# BG1094_MIPI_CAM.net
KiCad netlist of a schematic drawn in Altium Designer
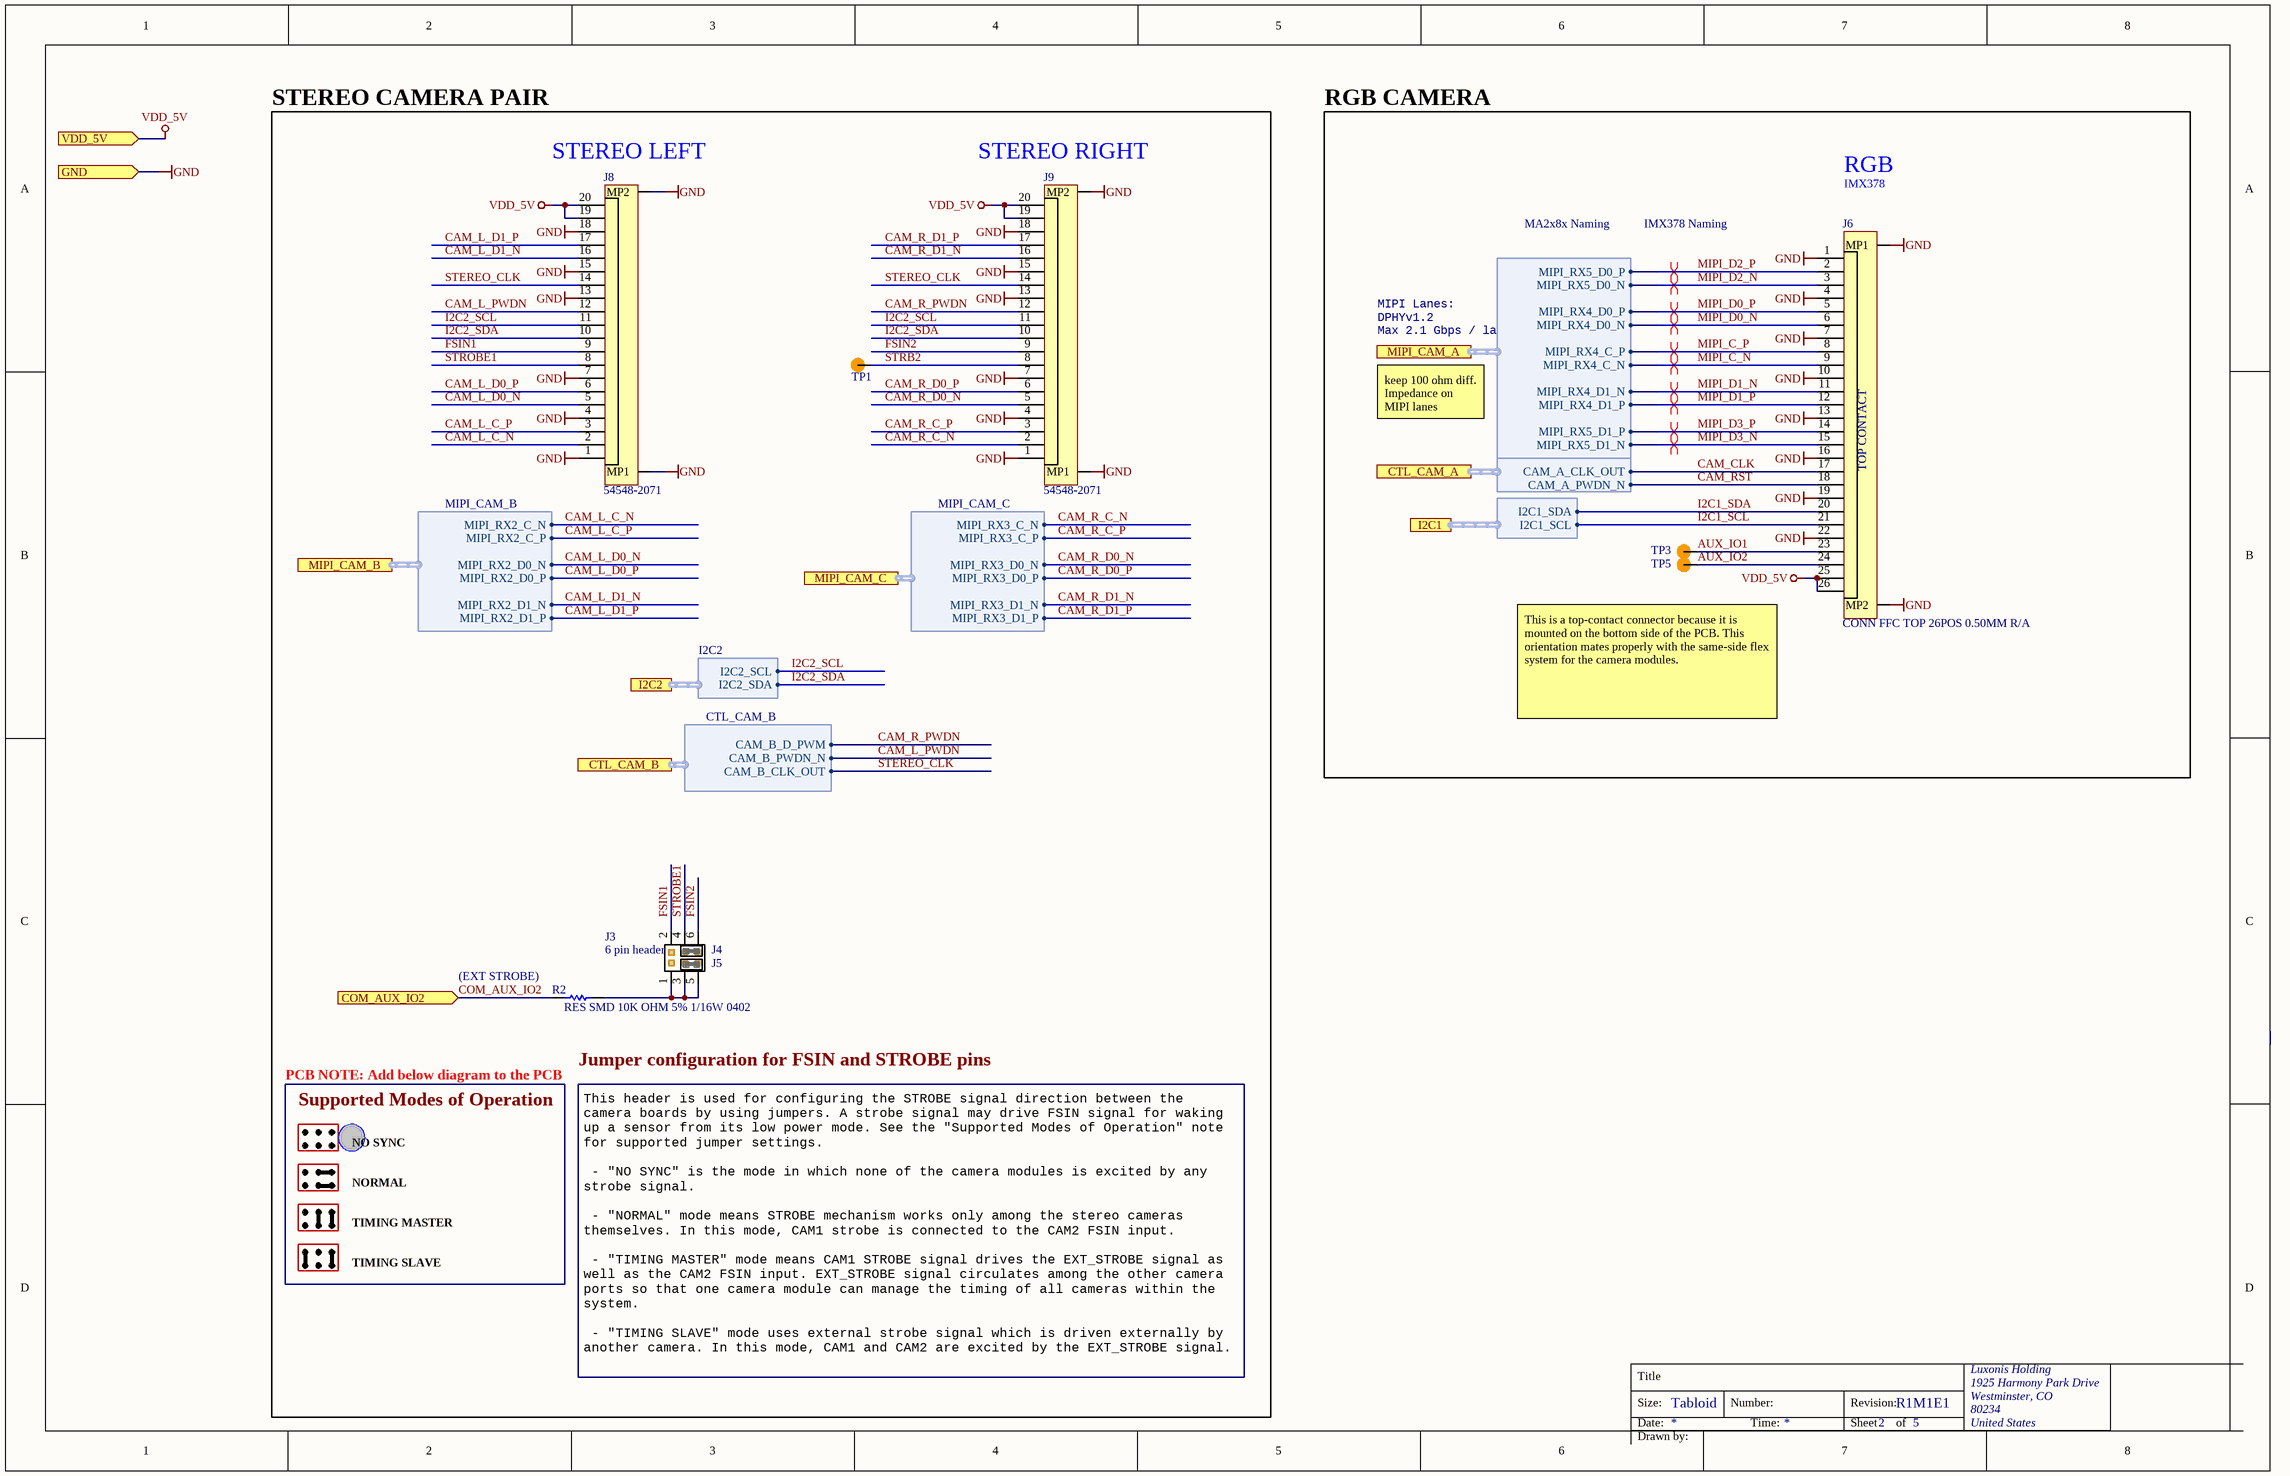
[diagram p0: BG1094_MIPI_CAM.SchDoc]

(export (version "E")
  (design (tool "Eeschema 10.0.6"))
  (components
    (comp (ref "J3")
      (value "6 pin header")
      (footprint "Luxonis:con-20021121-00006C4LF")
      (libsource (lib "Luxonis") (part "HDR_2x3_1.27mm"))
    )
    (comp (ref "J4")
      (value "1.27mm hdr shunt")
      (footprint "Luxonis:HDR_SHUNT_1.27MM")
      (description "CONN SHUNT 1.27MM BLACK (M50-1900005)")
      (libsource (lib "Luxonis") (part "HDR_Shunt_1.27mm"))
    )
    (comp (ref "J5")
      (value "1.27mm hdr shunt")
      (footprint "Luxonis:HDR_SHUNT_1.27MM")
      (description "CONN SHUNT 1.27MM BLACK (M50-1900005)")
      (libsource (lib "Luxonis") (part "HDR_Shunt_1.27mm"))
    )
    (comp (ref "J6")
      (value "CONN FFC TOP 26POS 0.50MM R/A")
      (footprint "BG1094:54550-2671")
      (libsource (lib "BG1094") (part "54550-2671"))
    )
    (comp (ref "J8")
      (value "54548-2071")
      (footprint "Luxonis:545482071")
      (description "FFC & FPC Connectors 0.5 FPC ZIF Hsg Assy ssy 20Ckt EmbsTp Pkg")
      (fields
        (field (name "MANUFACTURER_PART_NUMBER") "54548-2271")
        (field (name "MOUSER PART NUMBER") "538-54548-2271")
      )
      (libsource (lib "Luxonis") (part "54548-2071"))
    )
    (comp (ref "J9")
      (value "54548-2071")
      (footprint "Luxonis:545482071")
      (description "FFC & FPC Connectors 0.5 FPC ZIF Hsg Assy ssy 20Ckt EmbsTp Pkg")
      (fields
        (field (name "MANUFACTURER_PART_NUMBER") "54548-2271")
        (field (name "MOUSER PART NUMBER") "538-54548-2271")
      )
      (libsource (lib "Luxonis") (part "54548-2071"))
    )
    (comp (ref "R2")
      (value "RES SMD 10K OHM 5% 1/16W 0402")
      (footprint "RESC0402(1005)_N")
      (libsource (lib "Luxonis") (part "!RES"))
    )
    (comp (ref "TP1")
      (value "TP_SMD")
      (footprint "TP_0.75MM_SMD_NO-SILK")
      (description "circular pad test point, SMD")
      (libsource (lib "Luxonis") (part "TP_SMD"))
    )
    (comp (ref "TP3")
      (value "TP100_200_NS")
      (footprint "LuxonisMaster:TP100_200_NS")
      (libsource (lib "LuxonisMaster") (part "TEST_POINT"))
    )
    (comp (ref "TP5")
      (value "TP100_200_NS")
      (footprint "LuxonisMaster:TP100_200_NS")
      (libsource (lib "LuxonisMaster") (part "TEST_POINT"))
    )
  )
  (nets
    (net (code "8") (name "/AUX_IO1") (class "Default")
      (node (ref "J6") (pin "23") (pinfunction "23_23") (pintype "passive"))
      (node (ref "TP3") (pin "1") (pintype "passive"))
    )
    (net (code "9") (name "/AUX_IO2") (class "Default")
      (node (ref "J6") (pin "24") (pinfunction "24_24") (pintype "passive"))
      (node (ref "TP5") (pin "1") (pintype "passive"))
    )
    (net (code "10") (name "/CAM_CLK") (class "Default")
      (node (ref "J6") (pin "17") (pinfunction "17_17") (pintype "passive"))
    )
    (net (code "11") (name "/CAM_L_C_N") (class "Default")
      (node (ref "J8") (pin "2") (pinfunction "2_2") (pintype "passive"))
    )
    (net (code "12") (name "/CAM_L_C_P") (class "Default")
      (node (ref "J8") (pin "3") (pinfunction "3_3") (pintype "passive"))
    )
    (net (code "13") (name "/CAM_L_D0_N") (class "Default")
      (node (ref "J8") (pin "5") (pinfunction "5_5") (pintype "passive"))
    )
    (net (code "14") (name "/CAM_L_D0_P") (class "Default")
      (node (ref "J8") (pin "6") (pinfunction "6_6") (pintype "passive"))
    )
    (net (code "15") (name "/CAM_L_D1_N") (class "Default")
      (node (ref "J8") (pin "16") (pinfunction "16_16") (pintype "passive"))
    )
    (net (code "16") (name "/CAM_L_D1_P") (class "Default")
      (node (ref "J8") (pin "17") (pinfunction "17_17") (pintype "passive"))
    )
    (net (code "17") (name "/CAM_L_PWDN") (class "Default")
      (node (ref "J8") (pin "12") (pinfunction "12_12") (pintype "passive"))
    )
    (net (code "18") (name "/CAM_RST") (class "Default")
      (node (ref "J6") (pin "18") (pinfunction "18_18") (pintype "passive"))
    )
    (net (code "19") (name "/CAM_R_C_N") (class "Default")
      (node (ref "J9") (pin "2") (pinfunction "2_2") (pintype "passive"))
    )
    (net (code "20") (name "/CAM_R_C_P") (class "Default")
      (node (ref "J9") (pin "3") (pinfunction "3_3") (pintype "passive"))
    )
    (net (code "21") (name "/CAM_R_D0_N") (class "Default")
      (node (ref "J9") (pin "5") (pinfunction "5_5") (pintype "passive"))
    )
    (net (code "22") (name "/CAM_R_D0_P") (class "Default")
      (node (ref "J9") (pin "6") (pinfunction "6_6") (pintype "passive"))
    )
    (net (code "23") (name "/CAM_R_D1_N") (class "Default")
      (node (ref "J9") (pin "16") (pinfunction "16_16") (pintype "passive"))
    )
    (net (code "24") (name "/CAM_R_D1_P") (class "Default")
      (node (ref "J9") (pin "17") (pinfunction "17_17") (pintype "passive"))
    )
    (net (code "25") (name "/CAM_R_PWDN") (class "Default")
      (node (ref "J9") (pin "12") (pinfunction "12_12") (pintype "passive"))
    )
    (net (code "26") (name "/COM_AUX_IO2") (class "Default")
      (node (ref "R2") (pin "1") (pinfunction "1_1") (pintype "passive"))
    )
    (net (code "27") (name "/FSIN1") (class "Default")
      (node (ref "J3") (pin "2") (pinfunction "2_2") (pintype "passive"))
      (node (ref "J8") (pin "9") (pinfunction "9_9") (pintype "passive"))
    )
    (net (code "28") (name "/FSIN2") (class "Default")
      (node (ref "J3") (pin "6") (pinfunction "6_6") (pintype "passive"))
      (node (ref "J9") (pin "9") (pinfunction "9_9") (pintype "passive"))
    )
    (net (code "29") (name "/I2C1_SCL") (class "Default")
      (node (ref "J6") (pin "21") (pinfunction "21_21") (pintype "passive"))
    )
    (net (code "30") (name "/I2C1_SDA") (class "Default")
      (node (ref "J6") (pin "20") (pinfunction "20_20") (pintype "passive"))
    )
    (net (code "31") (name "/I2C2_SCL") (class "Default")
      (node (ref "J8") (pin "11") (pinfunction "11_11") (pintype "passive"))
      (node (ref "J9") (pin "11") (pinfunction "11_11") (pintype "passive"))
    )
    (net (code "32") (name "/I2C2_SDA") (class "Default")
      (node (ref "J8") (pin "10") (pinfunction "10_10") (pintype "passive"))
      (node (ref "J9") (pin "10") (pinfunction "10_10") (pintype "passive"))
    )
    (net (code "33") (name "/MIPI_C_N") (class "Default")
      (node (ref "J6") (pin "9") (pinfunction "9_9") (pintype "passive"))
    )
    (net (code "34") (name "/MIPI_C_P") (class "Default")
      (node (ref "J6") (pin "8") (pinfunction "8_8") (pintype "passive"))
    )
    (net (code "35") (name "/MIPI_D0_N") (class "Default")
      (node (ref "J6") (pin "6") (pinfunction "6_6") (pintype "passive"))
    )
    (net (code "36") (name "/MIPI_D0_P") (class "Default")
      (node (ref "J6") (pin "5") (pinfunction "5_5") (pintype "passive"))
    )
    (net (code "37") (name "/MIPI_D1_N") (class "Default")
      (node (ref "J6") (pin "11") (pinfunction "11_11") (pintype "passive"))
    )
    (net (code "38") (name "/MIPI_D1_P") (class "Default")
      (node (ref "J6") (pin "12") (pinfunction "12_12") (pintype "passive"))
    )
    (net (code "39") (name "/MIPI_D2_N") (class "Default")
      (node (ref "J6") (pin "3") (pinfunction "3_3") (pintype "passive"))
    )
    (net (code "40") (name "/MIPI_D2_P") (class "Default")
      (node (ref "J6") (pin "2") (pinfunction "2_2") (pintype "passive"))
    )
    (net (code "41") (name "/MIPI_D3_N") (class "Default")
      (node (ref "J6") (pin "15") (pinfunction "15_15") (pintype "passive"))
    )
    (net (code "42") (name "/MIPI_D3_P") (class "Default")
      (node (ref "J6") (pin "14") (pinfunction "14_14") (pintype "passive"))
    )
    (net (code "43") (name "/STEREO_CLK") (class "Default")
      (node (ref "J8") (pin "14") (pinfunction "14_14") (pintype "passive"))
      (node (ref "J9") (pin "14") (pinfunction "14_14") (pintype "passive"))
    )
    (net (code "44") (name "/STRB2") (class "Default")
      (node (ref "J9") (pin "8") (pinfunction "8_8") (pintype "passive"))
      (node (ref "TP1") (pin "1") (pintype "passive"))
    )
    (net (code "45") (name "/STROBE1") (class "Default")
      (node (ref "J3") (pin "4") (pinfunction "4_4") (pintype "passive"))
      (node (ref "J8") (pin "8") (pinfunction "8_8") (pintype "passive"))
    )
    (net (code "53") (name "GND") (class "Default")
      (node (ref "J6") (pin "1") (pinfunction "1_1") (pintype "passive"))
      (node (ref "J6") (pin "10") (pinfunction "10_10") (pintype "passive"))
      (node (ref "J6") (pin "13") (pinfunction "13_13") (pintype "passive"))
      (node (ref "J6") (pin "16") (pinfunction "16_16") (pintype "passive"))
      (node (ref "J6") (pin "19") (pinfunction "19_19") (pintype "passive"))
      (node (ref "J6") (pin "22") (pinfunction "22_22") (pintype "passive"))
      (node (ref "J6") (pin "4") (pinfunction "4_4") (pintype "passive"))
      (node (ref "J6") (pin "7") (pinfunction "7_7") (pintype "passive"))
      (node (ref "J6") (pin "MP1") (pinfunction "MP1_MP1") (pintype "passive"))
      (node (ref "J6") (pin "MP2") (pinfunction "MP2_MP2") (pintype "passive"))
      (node (ref "J8") (pin "1") (pinfunction "1_1") (pintype "passive"))
      (node (ref "J8") (pin "13") (pinfunction "13_13") (pintype "passive"))
      (node (ref "J8") (pin "15") (pinfunction "15_15") (pintype "passive"))
      (node (ref "J8") (pin "18") (pinfunction "18_18") (pintype "passive"))
      (node (ref "J8") (pin "4") (pinfunction "4_4") (pintype "passive"))
      (node (ref "J8") (pin "7") (pinfunction "7_7") (pintype "passive"))
      (node (ref "J8") (pin "MP1") (pinfunction "MP1_MP1") (pintype "passive"))
      (node (ref "J8") (pin "MP2") (pinfunction "MP2_MP2") (pintype "passive"))
      (node (ref "J9") (pin "1") (pinfunction "1_1") (pintype "passive"))
      (node (ref "J9") (pin "13") (pinfunction "13_13") (pintype "passive"))
      (node (ref "J9") (pin "15") (pinfunction "15_15") (pintype "passive"))
      (node (ref "J9") (pin "18") (pinfunction "18_18") (pintype "passive"))
      (node (ref "J9") (pin "4") (pinfunction "4_4") (pintype "passive"))
      (node (ref "J9") (pin "7") (pinfunction "7_7") (pintype "passive"))
      (node (ref "J9") (pin "MP1") (pinfunction "MP1_MP1") (pintype "passive"))
      (node (ref "J9") (pin "MP2") (pinfunction "MP2_MP2") (pintype "passive"))
    )
    (net (code "54") (name "Net-(J3-Pad1)") (class "Default")
      (node (ref "J3") (pin "1") (pinfunction "1_1") (pintype "passive"))
      (node (ref "J3") (pin "3") (pinfunction "3_3") (pintype "passive"))
      (node (ref "J3") (pin "5") (pinfunction "5_5") (pintype "passive"))
      (node (ref "R2") (pin "2") (pinfunction "2_2") (pintype "passive"))
    )
    (net (code "55") (name "VDD_5V") (class "Default")
      (node (ref "J6") (pin "25") (pinfunction "25_25") (pintype "passive"))
      (node (ref "J6") (pin "26") (pinfunction "26_26") (pintype "passive"))
      (node (ref "J8") (pin "19") (pinfunction "19_19") (pintype "passive"))
      (node (ref "J8") (pin "20") (pinfunction "20_20") (pintype "passive"))
      (node (ref "J9") (pin "19") (pinfunction "19_19") (pintype "passive"))
      (node (ref "J9") (pin "20") (pinfunction "20_20") (pintype "passive"))
    )
  )
)
